# Gate_Driver.net
KiCad netlist of a schematic drawn in Altium Designer
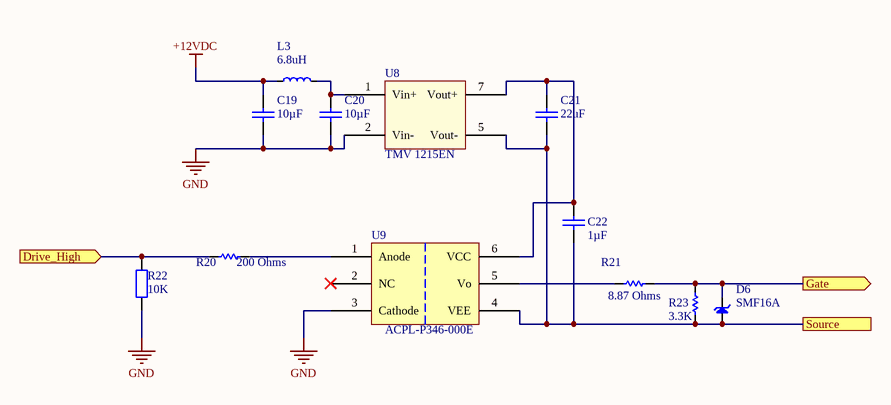
[diagram p0: Gate_Driver.SchDoc]

(export (version "E")
  (design (tool "Eeschema 10.0.6"))
  (components
    (comp (ref "C19")
      (value "10µF")
      (footprint "0603C")
      (description "CAP CER 10UF 16V X6S 0603")
      (fields
        (field (name "MANUFACTURER") "Murata Electronics")
        (field (name "MANUFACTURER PART NUMBER") "GRM188C81C106MA73D")
      )
      (libsource (lib "RELECTRIFY-PARTSlib_A") (part "Capacitor"))
    )
    (comp (ref "C20")
      (value "10µF")
      (footprint "0603C")
      (description "CAP CER 10UF 16V X6S 0603")
      (fields
        (field (name "MANUFACTURER") "Murata Electronics")
        (field (name "MANUFACTURER PART NUMBER") "GRM188C81C106MA73D")
      )
      (libsource (lib "RELECTRIFY-PARTSlib_A") (part "Capacitor"))
    )
    (comp (ref "C21")
      (value "22uF")
      (footprint "0805c")
      (description "CAP CER 2.2UF 25V X5R 0805")
      (fields
        (field (name "MANUFACTURER") "Samsung Electro-Mechanics")
        (field (name "MANUFACTURER PART NUMBER") "CL21A225KAFNNNG")
      )
      (libsource (lib "RELECTRIFY-PARTSlib_A") (part "Capacitor"))
    )
    (comp (ref "C22")
      (value "1µF")
      (footprint "0603C")
      (description "CAP CER 1UF 25V X7R 0603")
      (fields
        (field (name "MANUFACTURER") "Samsung Electro-Mechanics")
        (field (name "MANUFACTURER PART NUMBER") "CL10B105KA8NNNC")
      )
      (libsource (lib "RELECTRIFY-PARTSlib_A") (part "Capacitor"))
    )
    (comp (ref "D6")
      (value "SMF16A")
      (footprint "SOD-123H")
      (description "Zener Diode")
      (fields (field (name "VOLTAGE") "16V") (field (name "MANUFACTURER") "Littelfuse Inc."))
      (libsource (lib "Database_library") (part "Zener_Diode"))
    )
    (comp (ref "L3")
      (value "6.8uH")
      (footprint "1206R")
      (description "FIXED IND 6.8UH 380MA 170 MOHM")
      (fields
        (field (name "PARTNUMBER") "1002-0001")
        (field (name "MANUFACTURER PART NUMBER") "LB3218T6R8M")
        (field (name "X_CURRENT") "pcbs@relectrify.com")
      )
      (libsource (lib "RELECTRIFY-PARTSlib_A") (part "Inductor"))
    )
    (comp (ref "R20")
      (value "200 Ohms")
      (footprint "0603R")
      (description "RES 200 OHM 1% 1/8W 0603")
      (fields
        (field (name "MANUFACTURER") "Stackpole Electronics Inc")
        (field (name "MANUFACTURER PART NUMBER") "RNCP0603FTD200R")
      )
      (libsource (lib "RELECTRIFY-PARTSlib_A") (part "Resistor"))
    )
    (comp (ref "R21")
      (value "8.87 Ohms")
      (footprint "0805R")
      (description "RES 8.87 OHM 1% 1/8W 0805")
      (fields
        (field (name "MANUFACTURER") "Stackpole Electronics Inc")
        (field (name "MANUFACTURER PART NUMBER") "RMCF0805FT8R87")
      )
      (libsource (lib "RELECTRIFY-PARTSlib_A") (part "Resistor"))
    )
    (comp (ref "R22")
      (value "10K")
      (footprint "RES 0603/1608")
      (description "RES SMD 10K OHM 1% 1/10W 0603")
      (fields (field (name "PART NUMBER") "RC0603FR-0710KL") (field (name "TOLERANCE") "±1%"))
      (libsource (lib "electric_racing_lib") (part "Resistor"))
    )
    (comp (ref "R23")
      (value "3.3K")
      (footprint "0603R")
      (description "RES SMD 3.3K OHM 1% 1/10W 0603")
      (fields
        (field (name "MANUFACTURER") "Ralec Electronic Corporation")
        (field (name "MANUFACTURER PART NUMBER") "RTT033301FTP")
      )
      (libsource (lib "RELECTRIFY-PARTSlib_A") (part "Resistor"))
    )
    (comp (ref "U8")
      (value "TMV 1215EN")
      (footprint "TMVXXXXEN")
      (description "DC DC CONVERTER 15V 1W")
      (fields (field (name "MANUFACTURER") "Traco Power"))
      (libsource (lib "Schematic") (part "PDM-S"))
    )
    (comp (ref "U9")
      (value "ACPL-P346-000E")
      (footprint "ACPL-P346-000E")
      (description "OPTOISO 3.75KV 1CH GATE DRVR 6SO")
      (fields (field (name "PARTNUMBER") "1107-0007") (field (name "MANUFACTURER") "Broadcom Limited"))
      (libsource (lib "RELECTRIFY-PARTSlib_A") (part "ACPL-P346-000E"))
    )
  )
  (nets
    (net (code "1") (name "+12VDC") (class "Default")
      (node (ref "C19") (pin "1") (pinfunction "1_1") (pintype "passive"))
      (node (ref "L3") (pin "1") (pinfunction "1_1") (pintype "passive"))
    )
    (net (code "2") (name "/Drive_High") (class "Default")
      (node (ref "R20") (pin "1") (pinfunction "1_1") (pintype "passive"))
      (node (ref "R22") (pin "2") (pinfunction "2_2") (pintype "passive"))
    )
    (net (code "3") (name "/Gate") (class "Default")
      (node (ref "D6") (pin "K") (pinfunction "K_K") (pintype "passive"))
      (node (ref "R21") (pin "2") (pinfunction "2_2") (pintype "passive"))
      (node (ref "R23") (pin "2") (pinfunction "2_2") (pintype "passive"))
    )
    (net (code "4") (name "/Source") (class "Default")
      (node (ref "C21") (pin "2") (pinfunction "2_2") (pintype "passive"))
      (node (ref "C22") (pin "2") (pinfunction "2_2") (pintype "passive"))
      (node (ref "D6") (pin "A") (pinfunction "A_A") (pintype "passive"))
      (node (ref "R23") (pin "1") (pinfunction "1_1") (pintype "passive"))
      (node (ref "U8") (pin "5") (pinfunction "Vout-_5") (pintype "passive"))
      (node (ref "U9") (pin "4") (pinfunction "VEE_4") (pintype "passive"))
    )
    (net (code "5") (name "GND") (class "Default")
      (node (ref "C19") (pin "2") (pinfunction "2_2") (pintype "passive"))
      (node (ref "C20") (pin "2") (pinfunction "2_2") (pintype "passive"))
      (node (ref "R22") (pin "1") (pinfunction "1_1") (pintype "passive"))
      (node (ref "U8") (pin "2") (pinfunction "Vin-_2") (pintype "passive"))
      (node (ref "U9") (pin "3") (pinfunction "Cathode_3") (pintype "passive"))
    )
    (net (code "6") (name "Net-(U8-Vin+)") (class "Default")
      (node (ref "C20") (pin "1") (pinfunction "1_1") (pintype "passive"))
      (node (ref "L3") (pin "2") (pinfunction "2_2") (pintype "passive"))
      (node (ref "U8") (pin "1") (pinfunction "Vin+_1") (pintype "passive"))
    )
    (net (code "7") (name "Net-(U8-Vout+)") (class "Default")
      (node (ref "C21") (pin "1") (pinfunction "1_1") (pintype "passive"))
      (node (ref "C22") (pin "1") (pinfunction "1_1") (pintype "passive"))
      (node (ref "U8") (pin "7") (pinfunction "Vout+_7") (pintype "passive"))
      (node (ref "U9") (pin "6") (pinfunction "VCC_6") (pintype "passive"))
    )
    (net (code "8") (name "Net-(U9-Anode)") (class "Default")
      (node (ref "R20") (pin "2") (pinfunction "2_2") (pintype "passive"))
      (node (ref "U9") (pin "1") (pinfunction "Anode_1") (pintype "passive"))
    )
    (net (code "9") (name "Net-(U9-Vo)") (class "Default")
      (node (ref "R21") (pin "1") (pinfunction "1_1") (pintype "passive"))
      (node (ref "U9") (pin "5") (pinfunction "Vo_5") (pintype "passive"))
    )
    (net (code "10") (name "unconnected-(U9-NC-Pad2)") (class "Default")
      (node (ref "U9") (pin "2") (pinfunction "NC_2") (pintype "passive+no_connect"))
    )
  )
)
